# main.net
KiCad netlist of a schematic drawn in EAGLE
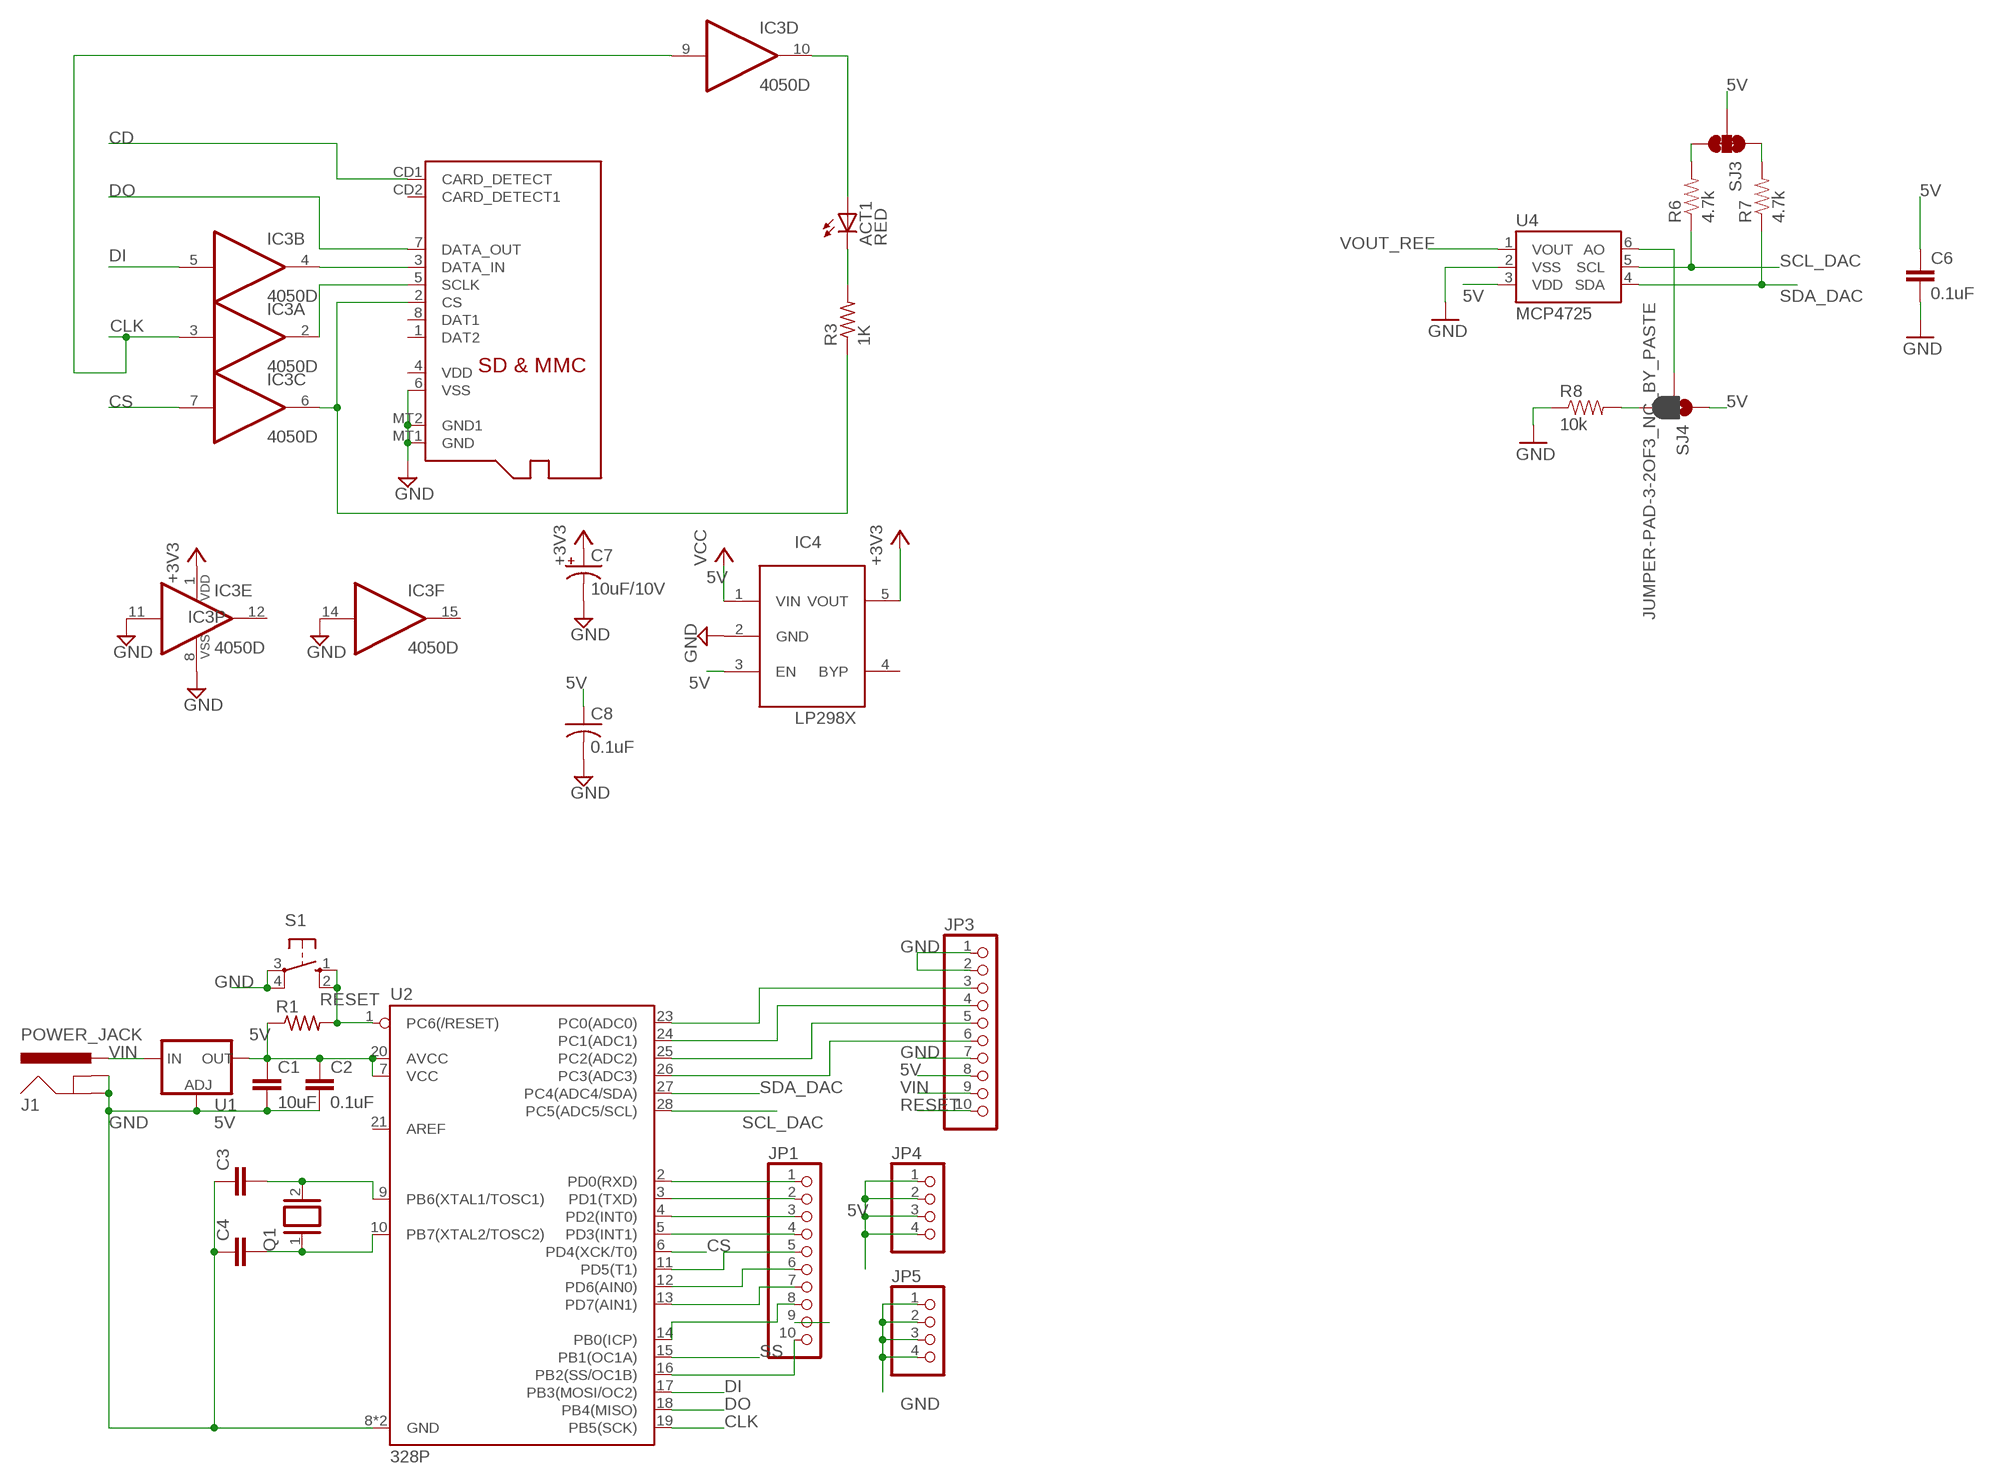
[diagram p0: schematic, sheet 1]

(export (version "E")
  (design (tool "Eeschema 10.0.6"))
  (components
    (comp (ref "ACT1")
      (value "RED")
      (footprint "eagle-import:CHIP-LED0805")
      (libsource (lib "eagle-import") (part "LEDCHIP-LED0805"))
    )
    (comp (ref "C1")
      (value "10uF")
      (footprint "eagle-import:C025-024X044")
      (libsource (lib "eagle-import") (part "C-EU025-024X044"))
    )
    (comp (ref "C2")
      (value "0.1uF")
      (footprint "eagle-import:C025-024X044")
      (libsource (lib "eagle-import") (part "C-EU025-024X044"))
    )
    (comp (ref "C3")
      (value "C-EU025-024X044")
      (footprint "eagle-import:C025-024X044")
      (libsource (lib "eagle-import") (part "C-EU025-024X044"))
    )
    (comp (ref "C4")
      (value "C-EU025-024X044")
      (footprint "eagle-import:C025-024X044")
      (libsource (lib "eagle-import") (part "C-EU025-024X044"))
    )
    (comp (ref "C6")
      (value "0.1uF")
      (footprint "eagle-import:0603-CAP")
      (libsource (lib "eagle-import") (part "CAP0603-CAP"))
    )
    (comp (ref "C7")
      (value "10uF/10V")
      (footprint "eagle-import:A_3216-18R")
      (libsource (lib "eagle-import") (part "CPOL-USA/3216-18R"))
    )
    (comp (ref "C8")
      (value "0.1uF")
      (footprint "eagle-import:C0805K")
      (libsource (lib "eagle-import") (part "C-USC0805K"))
    )
    (comp (ref "IC3")
      (value "4050D")
      (footprint "eagle-import:SO16")
      (libsource (lib "eagle-import") (part "4050D"))
    )
    (comp (ref "IC4")
      (value "LP298XS")
      (footprint "eagle-import:SOT23-5L")
      (libsource (lib "eagle-import") (part "LP298XS"))
    )
    (comp (ref "J1")
      (value "POWER_JACK")
      (footprint "eagle-import:POWER_JACK_PTH")
      (libsource (lib "eagle-import") (part "POWER_JACK"))
    )
    (comp (ref "JP1")
      (value "PINHD-1X10")
      (footprint "eagle-import:1X10")
      (libsource (lib "eagle-import") (part "PINHD-1X10"))
    )
    (comp (ref "JP3")
      (value "PINHD-1X10")
      (footprint "eagle-import:1X10")
      (libsource (lib "eagle-import") (part "PINHD-1X10"))
    )
    (comp (ref "JP4")
      (value "PINHD-1X4")
      (footprint "eagle-import:1X04")
      (libsource (lib "eagle-import") (part "PINHD-1X4"))
    )
    (comp (ref "JP5")
      (value "PINHD-1X4")
      (footprint "eagle-import:1X04")
      (libsource (lib "eagle-import") (part "PINHD-1X4"))
    )
    (comp (ref "Q1")
      (value "XTAL/S")
      (footprint "eagle-import:QS")
      (libsource (lib "eagle-import") (part "XTAL/S"))
    )
    (comp (ref "R1")
      (value "R-US_0204/7")
      (footprint "eagle-import:0204_7")
      (libsource (lib "eagle-import") (part "rcl_334_R-US_0204/7"))
    )
    (comp (ref "R3")
      (value "1K")
      (footprint "eagle-import:R0805")
      (libsource (lib "eagle-import") (part "R-US_R0805"))
    )
    (comp (ref "R6")
      (value "4.7k")
      (footprint "eagle-import:0603-RES")
      (libsource (lib "eagle-import") (part "RESISTOR0603-RES"))
    )
    (comp (ref "R7")
      (value "4.7k")
      (footprint "eagle-import:0603-RES")
      (libsource (lib "eagle-import") (part "RESISTOR0603-RES"))
    )
    (comp (ref "R8")
      (value "10k")
      (footprint "eagle-import:0603-RES")
      (libsource (lib "eagle-import") (part "RESISTOR0603-RES"))
    )
    (comp (ref "S1")
      (value "10-XX")
      (footprint "eagle-import:B3F-10XX")
      (fields (field (name "MPN") "B3F-1000"))
      (libsource (lib "eagle-import") (part "10-XX"))
    )
    (comp (ref "SJ3")
      (value "JUMPER-PAD-3-NC_BY_TRACE")
      (footprint "eagle-import:PAD-JUMPER-3-3OF3_NC_BY_TRACE_YES_SILK_FULL_BOX")
      (libsource (lib "eagle-import") (part "JUMPER-PAD-3-NC_BY_TRACE"))
    )
    (comp (ref "SJ4")
      (value "JUMPER-PAD-3-2OF3_NC_BY_PASTE")
      (footprint "eagle-import:PAD-JUMPER-3-2OF3_NC_BY_PASTE_YES_SILK_FULL_BOX")
      (libsource (lib "eagle-import") (part "JUMPER-PAD-3-2OF3_NC_BY_PASTE"))
    )
    (comp (ref "U1")
      (value "5V")
      (footprint "eagle-import:SOT223")
      (libsource (lib "eagle-import") (part "V_REG_LM1117SOT223"))
    )
    (comp (ref "U2")
      (value "328P")
      (footprint "eagle-import:DIP28")
      (libsource (lib "eagle-import") (part "ATMEGA328P_PDIP"))
    )
    (comp (ref "U4")
      (value "MCP4725")
      (footprint "eagle-import:SOT23-6")
      (libsource (lib "eagle-import") (part "MCP4725SOT-23"))
    )
    (comp (ref "X2")
      (value "MICROSD")
      (footprint "eagle-import:MICROSD")
      (libsource (lib "eagle-import") (part "MICROSD"))
    )
  )
  (nets
    (net (code "1") (name "+3V3") (class "Default")
      (node (ref "C7") (pin "+") (pinfunction "+_+") (pintype "passive"))
      (node (ref "IC3") (pin "1") (pinfunction "VDD_1") (pintype "power_in"))
      (node (ref "IC4") (pin "5") (pinfunction "VOUT_5") (pintype "bidirectional"))
    )
    (net (code "2") (name "/CD") (class "Default")
      (node (ref "X2") (pin "CD1") (pinfunction "CARD_DETECT_CD1") (pintype "passive"))
    )
    (net (code "3") (name "/CLK") (class "Default")
      (node (ref "IC3") (pin "3") (pinfunction "I_3") (pintype "input"))
      (node (ref "IC3") (pin "9") (pinfunction "I_9") (pintype "input"))
      (node (ref "U2") (pin "19") (pinfunction "PB5(SCK)_19") (pintype "bidirectional"))
    )
    (net (code "4") (name "/CS") (class "Default")
      (node (ref "IC3") (pin "7") (pinfunction "I_7") (pintype "input"))
      (node (ref "U2") (pin "6") (pinfunction "PD4(XCK/T0)_6") (pintype "bidirectional"))
    )
    (net (code "5") (name "/DI") (class "Default")
      (node (ref "IC3") (pin "5") (pinfunction "I_5") (pintype "input"))
      (node (ref "U2") (pin "17") (pinfunction "PB3(MOSI/OC2)_17") (pintype "bidirectional"))
    )
    (net (code "6") (name "/DO") (class "Default")
      (node (ref "U2") (pin "18") (pinfunction "PB4(MISO)_18") (pintype "bidirectional"))
      (node (ref "X2") (pin "7") (pinfunction "DATA_OUT_7") (pintype "output"))
    )
    (net (code "7") (name "/RESET") (class "Default")
      (node (ref "JP3") (pin "10") (pinfunction "10_10") (pintype "passive"))
      (node (ref "R1") (pin "2") (pinfunction "2_2") (pintype "passive"))
      (node (ref "S1") (pin "1") (pinfunction "S_1") (pintype "passive"))
      (node (ref "S1") (pin "2") (pinfunction "S1_2") (pintype "passive"))
      (node (ref "U2") (pin "1") (pinfunction "PC6(/RESET)_1") (pintype "bidirectional"))
    )
    (net (code "8") (name "/SCL_DAC") (class "Default")
      (node (ref "R6") (pin "1") (pinfunction "1_1") (pintype "passive"))
      (node (ref "U2") (pin "28") (pinfunction "PC5(ADC5/SCL)_28") (pintype "bidirectional"))
      (node (ref "U4") (pin "5") (pinfunction "SCL_5") (pintype "bidirectional"))
    )
    (net (code "9") (name "/SDA_DAC") (class "Default")
      (node (ref "R7") (pin "1") (pinfunction "1_1") (pintype "passive"))
      (node (ref "U2") (pin "27") (pinfunction "PC4(ADC4/SDA)_27") (pintype "bidirectional"))
      (node (ref "U4") (pin "4") (pinfunction "SDA_4") (pintype "bidirectional"))
    )
    (net (code "10") (name "/SS") (class "Default")
      (node (ref "JP1") (pin "9") (pinfunction "9_9") (pintype "passive"))
      (node (ref "U2") (pin "15") (pinfunction "PB1(OC1A)_15") (pintype "bidirectional"))
    )
    (net (code "11") (name "/VDD") (class "Default")
      (node (ref "X2") (pin "4") (pinfunction "VDD_4") (pintype "power_in"))
    )
    (net (code "12") (name "/VIN") (class "Default")
      (node (ref "J1") (pin "PWR") (pinfunction "PWR_PWR") (pintype "bidirectional"))
      (node (ref "JP3") (pin "9") (pinfunction "9_9") (pintype "passive"))
      (node (ref "U1") (pin "3") (pinfunction "IN_3") (pintype "input"))
    )
    (net (code "13") (name "/VOUT_REF") (class "Default")
      (node (ref "U4") (pin "1") (pinfunction "VOUT_1") (pintype "bidirectional"))
    )
    (net (code "14") (name "GND") (class "Default")
      (node (ref "C1") (pin "2") (pinfunction "2_2") (pintype "passive"))
      (node (ref "C2") (pin "2") (pinfunction "2_2") (pintype "passive"))
      (node (ref "C3") (pin "1") (pinfunction "1_1") (pintype "passive"))
      (node (ref "C4") (pin "1") (pinfunction "1_1") (pintype "passive"))
      (node (ref "C6") (pin "2") (pinfunction "2_2") (pintype "passive"))
      (node (ref "C7") (pin "-") (pinfunction "-_-") (pintype "passive"))
      (node (ref "C8") (pin "2") (pinfunction "2_2") (pintype "passive"))
      (node (ref "IC3") (pin "11") (pinfunction "I_11") (pintype "input"))
      (node (ref "IC3") (pin "14") (pinfunction "I_14") (pintype "input"))
      (node (ref "IC3") (pin "8") (pinfunction "VSS_8") (pintype "power_in"))
      (node (ref "IC4") (pin "2") (pinfunction "GND_2") (pintype "bidirectional"))
      (node (ref "J1") (pin "GND") (pinfunction "GND_GND") (pintype "bidirectional"))
      (node (ref "J1") (pin "GNDBREAK") (pinfunction "GNDBREAK_GNDBREAK") (pintype "bidirectional"))
      (node (ref "JP3") (pin "1") (pinfunction "1_1") (pintype "passive"))
      (node (ref "JP3") (pin "2") (pinfunction "2_2") (pintype "passive"))
      (node (ref "JP3") (pin "7") (pinfunction "7_7") (pintype "passive"))
      (node (ref "JP5") (pin "1") (pinfunction "1_1") (pintype "passive"))
      (node (ref "JP5") (pin "2") (pinfunction "2_2") (pintype "passive"))
      (node (ref "JP5") (pin "3") (pinfunction "3_3") (pintype "passive"))
      (node (ref "JP5") (pin "4") (pinfunction "4_4") (pintype "passive"))
      (node (ref "R8") (pin "1") (pinfunction "1_1") (pintype "passive"))
      (node (ref "S1") (pin "3") (pinfunction "P_3") (pintype "passive"))
      (node (ref "S1") (pin "4") (pinfunction "P1_4") (pintype "passive"))
      (node (ref "U1") (pin "1") (pinfunction "ADJ_1") (pintype "input"))
      (node (ref "U2") (pin "22") (pinfunction "GND_22") (pintype "bidirectional"))
      (node (ref "U2") (pin "8") (pinfunction "GND_8") (pintype "bidirectional"))
      (node (ref "U4") (pin "2") (pinfunction "VSS_2") (pintype "bidirectional"))
      (node (ref "X2") (pin "6") (pinfunction "VSS_6") (pintype "power_in"))
      (node (ref "X2") (pin "MT1") (pinfunction "GND_MT1") (pintype "power_in"))
      (node (ref "X2") (pin "MT2") (pinfunction "GND1_MT2") (pintype "power_in"))
    )
    (net (code "15") (name "Net-(ACT1-PadC)") (class "Default")
      (node (ref "ACT1") (pin "C") (pinfunction "C_C") (pintype "passive"))
      (node (ref "R3") (pin "2") (pinfunction "2_2") (pintype "passive"))
    )
    (net (code "16") (name "Net-(IC3A-O)") (class "Default")
      (node (ref "IC3") (pin "2") (pinfunction "O_2") (pintype "output"))
      (node (ref "X2") (pin "5") (pinfunction "SCLK_5") (pintype "input"))
    )
    (net (code "17") (name "Net-(IC3B-O)") (class "Default")
      (node (ref "IC3") (pin "4") (pinfunction "O_4") (pintype "output"))
      (node (ref "X2") (pin "3") (pinfunction "DATA_IN_3") (pintype "input"))
    )
    (net (code "18") (name "Net-(IC3C-O)") (class "Default")
      (node (ref "IC3") (pin "6") (pinfunction "O_6") (pintype "output"))
      (node (ref "R3") (pin "1") (pinfunction "1_1") (pintype "passive"))
      (node (ref "X2") (pin "2") (pinfunction "CS_2") (pintype "input"))
    )
    (net (code "19") (name "Net-(IC3D-O)") (class "Default")
      (node (ref "ACT1") (pin "A") (pinfunction "A_A") (pintype "passive"))
      (node (ref "IC3") (pin "10") (pinfunction "O_10") (pintype "output"))
    )
    (net (code "20") (name "Net-(R6-Pad2)") (class "Default")
      (node (ref "R6") (pin "2") (pinfunction "2_2") (pintype "passive"))
      (node (ref "SJ3") (pin "3") (pinfunction "3_3") (pintype "passive"))
    )
    (net (code "21") (name "Net-(R7-Pad2)") (class "Default")
      (node (ref "R7") (pin "2") (pinfunction "2_2") (pintype "passive"))
      (node (ref "SJ3") (pin "1") (pinfunction "1_1") (pintype "passive"))
    )
    (net (code "22") (name "Net-(R8-Pad2)") (class "Default")
      (node (ref "R8") (pin "2") (pinfunction "2_2") (pintype "passive"))
      (node (ref "SJ4") (pin "3") (pinfunction "3_3") (pintype "passive"))
    )
    (net (code "23") (name "Net-(U2-PB0(ICP))") (class "Default")
      (node (ref "JP1") (pin "8") (pinfunction "8_8") (pintype "passive"))
      (node (ref "U2") (pin "14") (pinfunction "PB0(ICP)_14") (pintype "bidirectional"))
    )
    (net (code "24") (name "Net-(U2-PB2(SS{slash}OC1B))") (class "Default")
      (node (ref "JP1") (pin "10") (pinfunction "10_10") (pintype "passive"))
      (node (ref "U2") (pin "16") (pinfunction "PB2(SS/OC1B)_16") (pintype "bidirectional"))
    )
    (net (code "25") (name "Net-(U2-PB6(XTAL1{slash}TOSC1))") (class "Default")
      (node (ref "C3") (pin "2") (pinfunction "2_2") (pintype "passive"))
      (node (ref "Q1") (pin "2") (pinfunction "2_2") (pintype "passive"))
      (node (ref "U2") (pin "9") (pinfunction "PB6(XTAL1/TOSC1)_9") (pintype "bidirectional"))
    )
    (net (code "26") (name "Net-(U2-PB7(XTAL2{slash}TOSC2))") (class "Default")
      (node (ref "C4") (pin "2") (pinfunction "2_2") (pintype "passive"))
      (node (ref "Q1") (pin "1") (pinfunction "1_1") (pintype "passive"))
      (node (ref "U2") (pin "10") (pinfunction "PB7(XTAL2/TOSC2)_10") (pintype "bidirectional"))
    )
    (net (code "27") (name "Net-(U2-PC1(ADC1))") (class "Default")
      (node (ref "JP3") (pin "4") (pinfunction "4_4") (pintype "passive"))
      (node (ref "U2") (pin "24") (pinfunction "PC1(ADC1)_24") (pintype "bidirectional"))
    )
    (net (code "28") (name "Net-(U2-PC2(ADC2))") (class "Default")
      (node (ref "JP3") (pin "5") (pinfunction "5_5") (pintype "passive"))
      (node (ref "U2") (pin "25") (pinfunction "PC2(ADC2)_25") (pintype "bidirectional"))
    )
    (net (code "29") (name "Net-(U2-PC3(ADC3))") (class "Default")
      (node (ref "JP3") (pin "6") (pinfunction "6_6") (pintype "passive"))
      (node (ref "U2") (pin "26") (pinfunction "PC3(ADC3)_26") (pintype "bidirectional"))
    )
    (net (code "30") (name "Net-(U2-PD0(RXD))") (class "Default")
      (node (ref "JP1") (pin "1") (pinfunction "1_1") (pintype "passive"))
      (node (ref "U2") (pin "2") (pinfunction "PD0(RXD)_2") (pintype "bidirectional"))
    )
    (net (code "31") (name "Net-(U2-PD1(TXD))") (class "Default")
      (node (ref "JP1") (pin "2") (pinfunction "2_2") (pintype "passive"))
      (node (ref "U2") (pin "3") (pinfunction "PD1(TXD)_3") (pintype "bidirectional"))
    )
    (net (code "32") (name "Net-(U2-PD2(INT0))") (class "Default")
      (node (ref "JP1") (pin "3") (pinfunction "3_3") (pintype "passive"))
      (node (ref "U2") (pin "4") (pinfunction "PD2(INT0)_4") (pintype "bidirectional"))
    )
    (net (code "33") (name "Net-(U2-PD3(INT1))") (class "Default")
      (node (ref "JP1") (pin "4") (pinfunction "4_4") (pintype "passive"))
      (node (ref "U2") (pin "5") (pinfunction "PD3(INT1)_5") (pintype "bidirectional"))
    )
    (net (code "34") (name "Net-(U2-PD5(T1))") (class "Default")
      (node (ref "JP1") (pin "5") (pinfunction "5_5") (pintype "passive"))
      (node (ref "U2") (pin "11") (pinfunction "PD5(T1)_11") (pintype "bidirectional"))
    )
    (net (code "35") (name "Net-(U2-PD6(AIN0))") (class "Default")
      (node (ref "JP1") (pin "6") (pinfunction "6_6") (pintype "passive"))
      (node (ref "U2") (pin "12") (pinfunction "PD6(AIN0)_12") (pintype "bidirectional"))
    )
    (net (code "36") (name "Net-(U2-PD7(AIN1))") (class "Default")
      (node (ref "JP1") (pin "7") (pinfunction "7_7") (pintype "passive"))
      (node (ref "U2") (pin "13") (pinfunction "PD7(AIN1)_13") (pintype "bidirectional"))
    )
    (net (code "37") (name "Net-(U4-AO)") (class "Default")
      (node (ref "SJ4") (pin "2") (pinfunction "2_2") (pintype "passive"))
      (node (ref "U4") (pin "6") (pinfunction "AO_6") (pintype "bidirectional"))
    )
    (net (code "38") (name "VCC") (class "Default")
      (node (ref "C1") (pin "1") (pinfunction "1_1") (pintype "passive"))
      (node (ref "C2") (pin "1") (pinfunction "1_1") (pintype "passive"))
      (node (ref "C6") (pin "1") (pinfunction "1_1") (pintype "passive"))
      (node (ref "C8") (pin "1") (pinfunction "1_1") (pintype "passive"))
      (node (ref "IC4") (pin "1") (pinfunction "VIN_1") (pintype "bidirectional"))
      (node (ref "IC4") (pin "3") (pinfunction "EN_3") (pintype "bidirectional"))
      (node (ref "JP3") (pin "8") (pinfunction "8_8") (pintype "passive"))
      (node (ref "JP4") (pin "1") (pinfunction "1_1") (pintype "passive"))
      (node (ref "JP4") (pin "2") (pinfunction "2_2") (pintype "passive"))
      (node (ref "JP4") (pin "3") (pinfunction "3_3") (pintype "passive"))
      (node (ref "JP4") (pin "4") (pinfunction "4_4") (pintype "passive"))
      (node (ref "R1") (pin "1") (pinfunction "1_1") (pintype "passive"))
      (node (ref "SJ3") (pin "2") (pinfunction "2_2") (pintype "passive"))
      (node (ref "SJ4") (pin "1") (pinfunction "1_1") (pintype "passive"))
      (node (ref "U1") (pin "2") (pinfunction "OUT_2") (pintype "output"))
      (node (ref "U1") (pin "4") (pinfunction "OUT_4") (pintype "output"))
      (node (ref "U2") (pin "20") (pinfunction "AVCC_20") (pintype "bidirectional"))
      (node (ref "U2") (pin "7") (pinfunction "VCC_7") (pintype "bidirectional"))
      (node (ref "U4") (pin "3") (pinfunction "VDD_3") (pintype "bidirectional"))
    )
    (net (code "39") (name "unconnected-(IC3E-O-Pad12)") (class "Default")
      (node (ref "IC3") (pin "12") (pinfunction "O_12") (pintype "output"))
    )
    (net (code "40") (name "unconnected-(IC3F-O-Pad15)") (class "Default")
      (node (ref "IC3") (pin "15") (pinfunction "O_15") (pintype "output"))
    )
    (net (code "41") (name "unconnected-(IC4-BYP-Pad4)") (class "Default")
      (node (ref "IC4") (pin "4") (pinfunction "BYP_4") (pintype "bidirectional"))
    )
    (net (code "42") (name "unconnected-(JP3-Pad3)") (class "Default")
      (node (ref "JP3") (pin "3") (pinfunction "3_3") (pintype "passive"))
    )
    (net (code "43") (name "unconnected-(U2-AREF-Pad21)") (class "Default")
      (node (ref "U2") (pin "21") (pinfunction "AREF_21") (pintype "bidirectional"))
    )
    (net (code "44") (name "unconnected-(U2-PC0(ADC0)-Pad23)") (class "Default")
      (node (ref "U2") (pin "23") (pinfunction "PC0(ADC0)_23") (pintype "bidirectional"))
    )
    (net (code "45") (name "unconnected-(X2-CARD_DETECT1-PadCD2)") (class "Default")
      (node (ref "X2") (pin "CD2") (pinfunction "CARD_DETECT1_CD2") (pintype "passive"))
    )
    (net (code "46") (name "unconnected-(X2-DAT1-Pad8)") (class "Default")
      (node (ref "X2") (pin "8") (pinfunction "DAT1_8") (pintype "bidirectional"))
    )
    (net (code "47") (name "unconnected-(X2-DAT2-Pad1)") (class "Default")
      (node (ref "X2") (pin "1") (pinfunction "DAT2_1") (pintype "bidirectional"))
    )
  )
)
